# 5v.net
KiCad netlist of a schematic drawn in Altium Designer
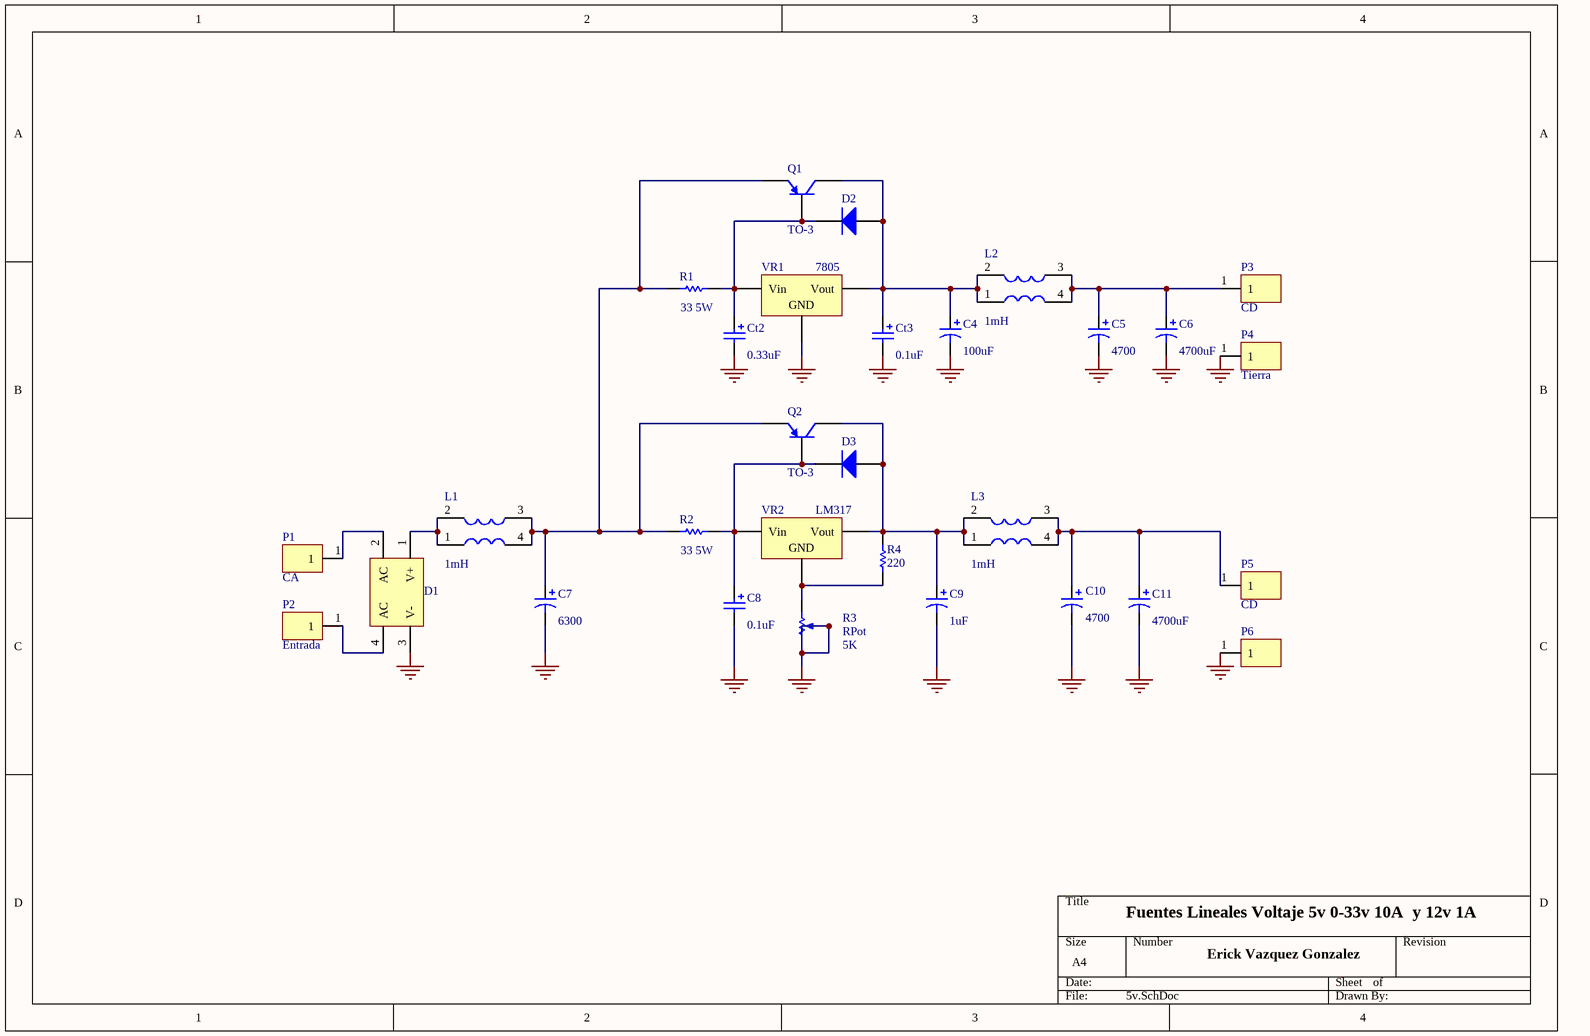
[diagram p0: 5v.SchDoc]

(export (version "E")
  (design (tool "Eeschema 10.0.6"))
  (components
    (comp (ref "C4")
      (value "100uF")
      (footprint "RAD-0.2")
      (description "Polarized Capacitor (Radial)")
      (fields (field (name "Comment") "Cap Pol2") (field (name "PUBLISHER") "Altium Limited"))
      (libsource (lib "Miscellaneous Devices") (part "Cap Pol1"))
    )
    (comp (ref "C5")
      (value "4700")
      (footprint "CAP4700")
      (description "Polarized Capacitor (Radial)")
      (fields (field (name "Comment") "Cap Pol1") (field (name "PUBLISHER") "Altium Limited"))
      (libsource (lib "Miscellaneous Devices") (part "Cap Pol1"))
    )
    (comp (ref "C6")
      (value "4700uF")
      (footprint "CAP4700")
      (description "Polarized Capacitor (Radial)")
      (fields (field (name "Comment") "Cap Pol1") (field (name "PUBLISHER") "Altium Limited"))
      (libsource (lib "Miscellaneous Devices") (part "Cap Pol1"))
    )
    (comp (ref "C7")
      (value "6300")
      (footprint "Cap6800u")
      (description "Polarized Capacitor (Radial)")
      (fields (field (name "Comment") "Cap Pol1") (field (name "PUBLISHER") "Altium Limited"))
      (libsource (lib "Miscellaneous Devices") (part "Cap Pol1"))
    )
    (comp (ref "C8")
      (value "0.1uF")
      (footprint "RAD-0.2")
      (description "Polarized Capacitor (Axial)")
      (fields (field (name "Comment") "Cap Tan") (field (name "PUBLISHER") "Altium Limited"))
      (libsource (lib "Miscellaneous Devices") (part "Cap Pol2"))
    )
    (comp (ref "C9")
      (value "1uF")
      (footprint "RAD-0.2")
      (description "Polarized Capacitor (Radial)")
      (fields (field (name "Comment") "Cap Pol2") (field (name "PUBLISHER") "Altium Limited"))
      (libsource (lib "Miscellaneous Devices") (part "Cap Pol1"))
    )
    (comp (ref "C10")
      (value "4700")
      (footprint "CAP4700")
      (description "Polarized Capacitor (Radial)")
      (fields (field (name "Comment") "Cap Pol1") (field (name "PUBLISHER") "Altium Limited"))
      (libsource (lib "Miscellaneous Devices") (part "Cap Pol1"))
    )
    (comp (ref "C11")
      (value "4700uF")
      (footprint "CAP4700")
      (description "Polarized Capacitor (Radial)")
      (fields (field (name "Comment") "Cap Pol1") (field (name "PUBLISHER") "Altium Limited"))
      (libsource (lib "Miscellaneous Devices") (part "Cap Pol1"))
    )
    (comp (ref "Ct2")
      (value "0.33uF")
      (footprint "RAD-0.2")
      (description "Polarized Capacitor (Axial)")
      (fields (field (name "Comment") "Cap Tan") (field (name "PUBLISHER") "Altium Limited"))
      (libsource (lib "Miscellaneous Devices") (part "Cap Pol2"))
    )
    (comp (ref "Ct3")
      (value "0.1uF")
      (footprint "RAD-0.2")
      (description "Polarized Capacitor (Axial)")
      (fields (field (name "Comment") "Cap Tan") (field (name "PUBLISHER") "Altium Limited"))
      (libsource (lib "Miscellaneous Devices") (part "Cap Pol2"))
    )
    (comp (ref "D1")
      (value "Bridge2")
      (footprint "PuenteD 25A:PCBComponent_1")
      (description "Diode Bridge")
      (fields (field (name "PUBLISHER") "Altium Limited"))
      (libsource (lib "Miscellaneous Devices") (part "Bridge2"))
    )
    (comp (ref "D2")
      (value "Diodo")
      (footprint "URDiodo:SuperDiodo")
      (description "3 Amp Medium Power Silicon Rectifier Diode")
      (fields (field (name "PUBLISHER") "Altium Limited"))
      (libsource (lib "Miscellaneous Devices") (part "Diode 1N5408"))
    )
    (comp (ref "D3")
      (value "Diodo")
      (footprint "SuperDiodo")
      (description "3 Amp Medium Power Silicon Rectifier Diode")
      (fields (field (name "PUBLISHER") "Altium Limited"))
      (libsource (lib "Miscellaneous Devices") (part "Diode 1N5408"))
    )
    (comp (ref "L1") (value "1mH") (footprint "Bobina") (libsource (lib "Bobina 25A") (part "Bobina")))
    (comp (ref "L2") (value "1mH") (footprint "Bobina") (libsource (lib "Bobina 25A") (part "Bobina")))
    (comp (ref "L3") (value "1mH") (footprint "Bobina") (libsource (lib "Bobina 25A") (part "Bobina")))
    (comp (ref "P1") (value "CA") (footprint "MOLEX") (libsource (lib "") (part "Component_1_1")))
    (comp (ref "P2") (value "Entrada") (footprint "MOLEX") (libsource (lib "") (part "Component_1_1")))
    (comp (ref "P3") (value "CD") (footprint "MOLEX") (libsource (lib "Conector") (part "Component_1")))
    (comp (ref "P4") (value "Tierra") (footprint "MOLEX") (libsource (lib "Conector") (part "Component_1")))
    (comp (ref "P5") (value "CD") (footprint "MOLEX") (libsource (lib "Conector") (part "Component_1")))
    (comp (ref "P6") (value "~") (footprint "MOLEX") (libsource (lib "Conector") (part "Component_1")))
    (comp (ref "Q1")
      (value "TO-3")
      (footprint "to3")
      (description "PNP Bipolar Transistor")
      (fields (field (name "PUBLISHER") "Altium Limited"))
      (libsource (lib "Miscellaneous Devices") (part "PNP"))
    )
    (comp (ref "Q2")
      (value "TO-3")
      (footprint "to3")
      (description "PNP Bipolar Transistor")
      (fields (field (name "PUBLISHER") "Altium Limited"))
      (libsource (lib "Miscellaneous Devices") (part "PNP"))
    )
    (comp (ref "R1")
      (value "33 5W")
      (footprint "Resist 10W")
      (description "Resistor")
      (fields (field (name "Comment") "Res111") (field (name "PUBLISHER") "Altium Limited"))
      (libsource (lib "Miscellaneous Devices") (part "Res1"))
    )
    (comp (ref "R2")
      (value "33 5W")
      (footprint "Resist 10W")
      (description "Resistor")
      (fields (field (name "R2") "33 5W") (field (name "PUBLISHER") "Altium Limited"))
      (libsource (lib "Miscellaneous Devices") (part "Res1"))
    )
    (comp (ref "R3")
      (value "RPot")
      (footprint "POT2")
      (description "Potentiometer")
      (fields (field (name "ALTIUM_VALUE") "5K") (field (name "PUBLISHER") "Altium Limited"))
      (libsource (lib "Miscellaneous Devices") (part "RPot"))
    )
    (comp (ref "R4")
      (value "220")
      (footprint "AXIAL-0.3")
      (description "Resistor")
      (fields (field (name "Comment") "Res1") (field (name "PUBLISHER") "Altium Limited"))
      (libsource (lib "Miscellaneous Devices") (part "Res1"))
    )
    (comp (ref "VR1")
      (value "7805")
      (footprint "HEATSINK")
      (description "Voltage Regulator")
      (fields (field (name "PUBLISHER") "Altium Limited"))
      (libsource (lib "Miscellaneous Devices") (part "Volt Reg"))
    )
    (comp (ref "VR2")
      (value "LM317")
      (footprint "HEATSINK")
      (description "Voltage Regulator")
      (fields (field (name "PUBLISHER") "Altium Limited"))
      (libsource (lib "Miscellaneous Devices") (part "Volt Reg"))
    )
  )
  (nets
    (net (code "1") (name "GND") (class "Default")
      (node (ref "C10") (pin "2") (pinfunction "2_2") (pintype "passive"))
      (node (ref "C11") (pin "2") (pinfunction "2_2") (pintype "passive"))
      (node (ref "C4") (pin "2") (pinfunction "2_2") (pintype "passive"))
      (node (ref "C5") (pin "2") (pinfunction "2_2") (pintype "passive"))
      (node (ref "C6") (pin "2") (pinfunction "2_2") (pintype "passive"))
      (node (ref "C7") (pin "2") (pinfunction "2_2") (pintype "passive"))
      (node (ref "C8") (pin "2") (pinfunction "2_2") (pintype "passive"))
      (node (ref "C9") (pin "2") (pinfunction "2_2") (pintype "passive"))
      (node (ref "Ct2") (pin "2") (pinfunction "2_2") (pintype "passive"))
      (node (ref "Ct3") (pin "2") (pinfunction "2_2") (pintype "passive"))
      (node (ref "D1") (pin "3") (pinfunction "V-_3") (pintype "passive"))
      (node (ref "P4") (pin "1") (pinfunction "1_1") (pintype "passive"))
      (node (ref "P6") (pin "1") (pinfunction "1_1") (pintype "passive"))
      (node (ref "R3") (pin "1") (pinfunction "TOP_1") (pintype "passive"))
      (node (ref "R3") (pin "3") (pinfunction "TAP_3") (pintype "passive"))
      (node (ref "VR1") (pin "2") (pinfunction "GND_2") (pintype "passive"))
    )
    (net (code "2") (name "Net-(C5-Pad1)") (class "Default")
      (node (ref "C5") (pin "1") (pinfunction "1_1") (pintype "passive"))
      (node (ref "C6") (pin "1") (pinfunction "1_1") (pintype "passive"))
      (node (ref "L2") (pin "3") (pinfunction "3_3") (pintype "passive"))
      (node (ref "L2") (pin "4") (pinfunction "4_4") (pintype "passive"))
      (node (ref "P3") (pin "1") (pinfunction "1_1") (pintype "passive"))
    )
    (net (code "3") (name "Net-(C10-Pad1)") (class "Default")
      (node (ref "C10") (pin "1") (pinfunction "1_1") (pintype "passive"))
      (node (ref "C11") (pin "1") (pinfunction "1_1") (pintype "passive"))
      (node (ref "L3") (pin "3") (pinfunction "3_3") (pintype "passive"))
      (node (ref "L3") (pin "4") (pinfunction "4_4") (pintype "passive"))
      (node (ref "P5") (pin "1") (pinfunction "1_1") (pintype "passive"))
    )
    (net (code "4") (name "Net-(D1-AC-Pad2)") (class "Default")
      (node (ref "D1") (pin "2") (pinfunction "AC_2") (pintype "passive"))
      (node (ref "P1") (pin "1") (pinfunction "1_1") (pintype "passive"))
    )
    (net (code "5") (name "Net-(D1-AC-Pad4)") (class "Default")
      (node (ref "D1") (pin "4") (pinfunction "AC_4") (pintype "passive"))
      (node (ref "P2") (pin "1") (pinfunction "1_1") (pintype "passive"))
    )
    (net (code "6") (name "Net-(D1-V+)") (class "Default")
      (node (ref "D1") (pin "1") (pinfunction "V+_1") (pintype "passive"))
      (node (ref "L1") (pin "1") (pinfunction "1_1") (pintype "passive"))
      (node (ref "L1") (pin "2") (pinfunction "2_2") (pintype "passive"))
    )
    (net (code "7") (name "Net-(D2-A)") (class "Default")
      (node (ref "C4") (pin "1") (pinfunction "1_1") (pintype "passive"))
      (node (ref "Ct3") (pin "1") (pinfunction "1_1") (pintype "passive"))
      (node (ref "D2") (pin "1") (pinfunction "A_1") (pintype "passive"))
      (node (ref "L2") (pin "1") (pinfunction "1_1") (pintype "passive"))
      (node (ref "L2") (pin "2") (pinfunction "2_2") (pintype "passive"))
      (node (ref "Q1") (pin "1") (pinfunction "C_1") (pintype "passive"))
      (node (ref "VR1") (pin "3") (pinfunction "Vout_3") (pintype "passive"))
    )
    (net (code "8") (name "Net-(D2-K)") (class "Default")
      (node (ref "Ct2") (pin "1") (pinfunction "1_1") (pintype "passive"))
      (node (ref "D2") (pin "2") (pinfunction "K_2") (pintype "passive"))
      (node (ref "Q1") (pin "2") (pinfunction "B_2") (pintype "passive"))
      (node (ref "R1") (pin "2") (pinfunction "2_2") (pintype "passive"))
      (node (ref "VR1") (pin "1") (pinfunction "Vin_1") (pintype "passive"))
    )
    (net (code "9") (name "Net-(D3-A)") (class "Default")
      (node (ref "C9") (pin "1") (pinfunction "1_1") (pintype "passive"))
      (node (ref "D3") (pin "1") (pinfunction "A_1") (pintype "passive"))
      (node (ref "L3") (pin "1") (pinfunction "1_1") (pintype "passive"))
      (node (ref "L3") (pin "2") (pinfunction "2_2") (pintype "passive"))
      (node (ref "Q2") (pin "1") (pinfunction "C_1") (pintype "passive"))
      (node (ref "R4") (pin "2") (pinfunction "2_2") (pintype "passive"))
      (node (ref "VR2") (pin "3") (pinfunction "Vout_3") (pintype "passive"))
    )
    (net (code "10") (name "Net-(D3-K)") (class "Default")
      (node (ref "C8") (pin "1") (pinfunction "1_1") (pintype "passive"))
      (node (ref "D3") (pin "2") (pinfunction "K_2") (pintype "passive"))
      (node (ref "Q2") (pin "2") (pinfunction "B_2") (pintype "passive"))
      (node (ref "R2") (pin "2") (pinfunction "2_2") (pintype "passive"))
      (node (ref "VR2") (pin "1") (pinfunction "Vin_1") (pintype "passive"))
    )
    (net (code "11") (name "Net-(Q1-E)") (class "Default")
      (node (ref "C7") (pin "1") (pinfunction "1_1") (pintype "passive"))
      (node (ref "L1") (pin "3") (pinfunction "3_3") (pintype "passive"))
      (node (ref "L1") (pin "4") (pinfunction "4_4") (pintype "passive"))
      (node (ref "Q1") (pin "3") (pinfunction "E_3") (pintype "passive"))
      (node (ref "Q2") (pin "3") (pinfunction "E_3") (pintype "passive"))
      (node (ref "R1") (pin "1") (pinfunction "1_1") (pintype "passive"))
      (node (ref "R2") (pin "1") (pinfunction "1_1") (pintype "passive"))
    )
    (net (code "12") (name "Net-(R3-BOT)") (class "Default")
      (node (ref "R3") (pin "2") (pinfunction "BOT_2") (pintype "passive"))
      (node (ref "R4") (pin "1") (pinfunction "1_1") (pintype "passive"))
      (node (ref "VR2") (pin "2") (pinfunction "GND_2") (pintype "passive"))
    )
  )
)
